# IO_Carte_Nucleo2.net
KiCad netlist of a schematic drawn in Altium Designer
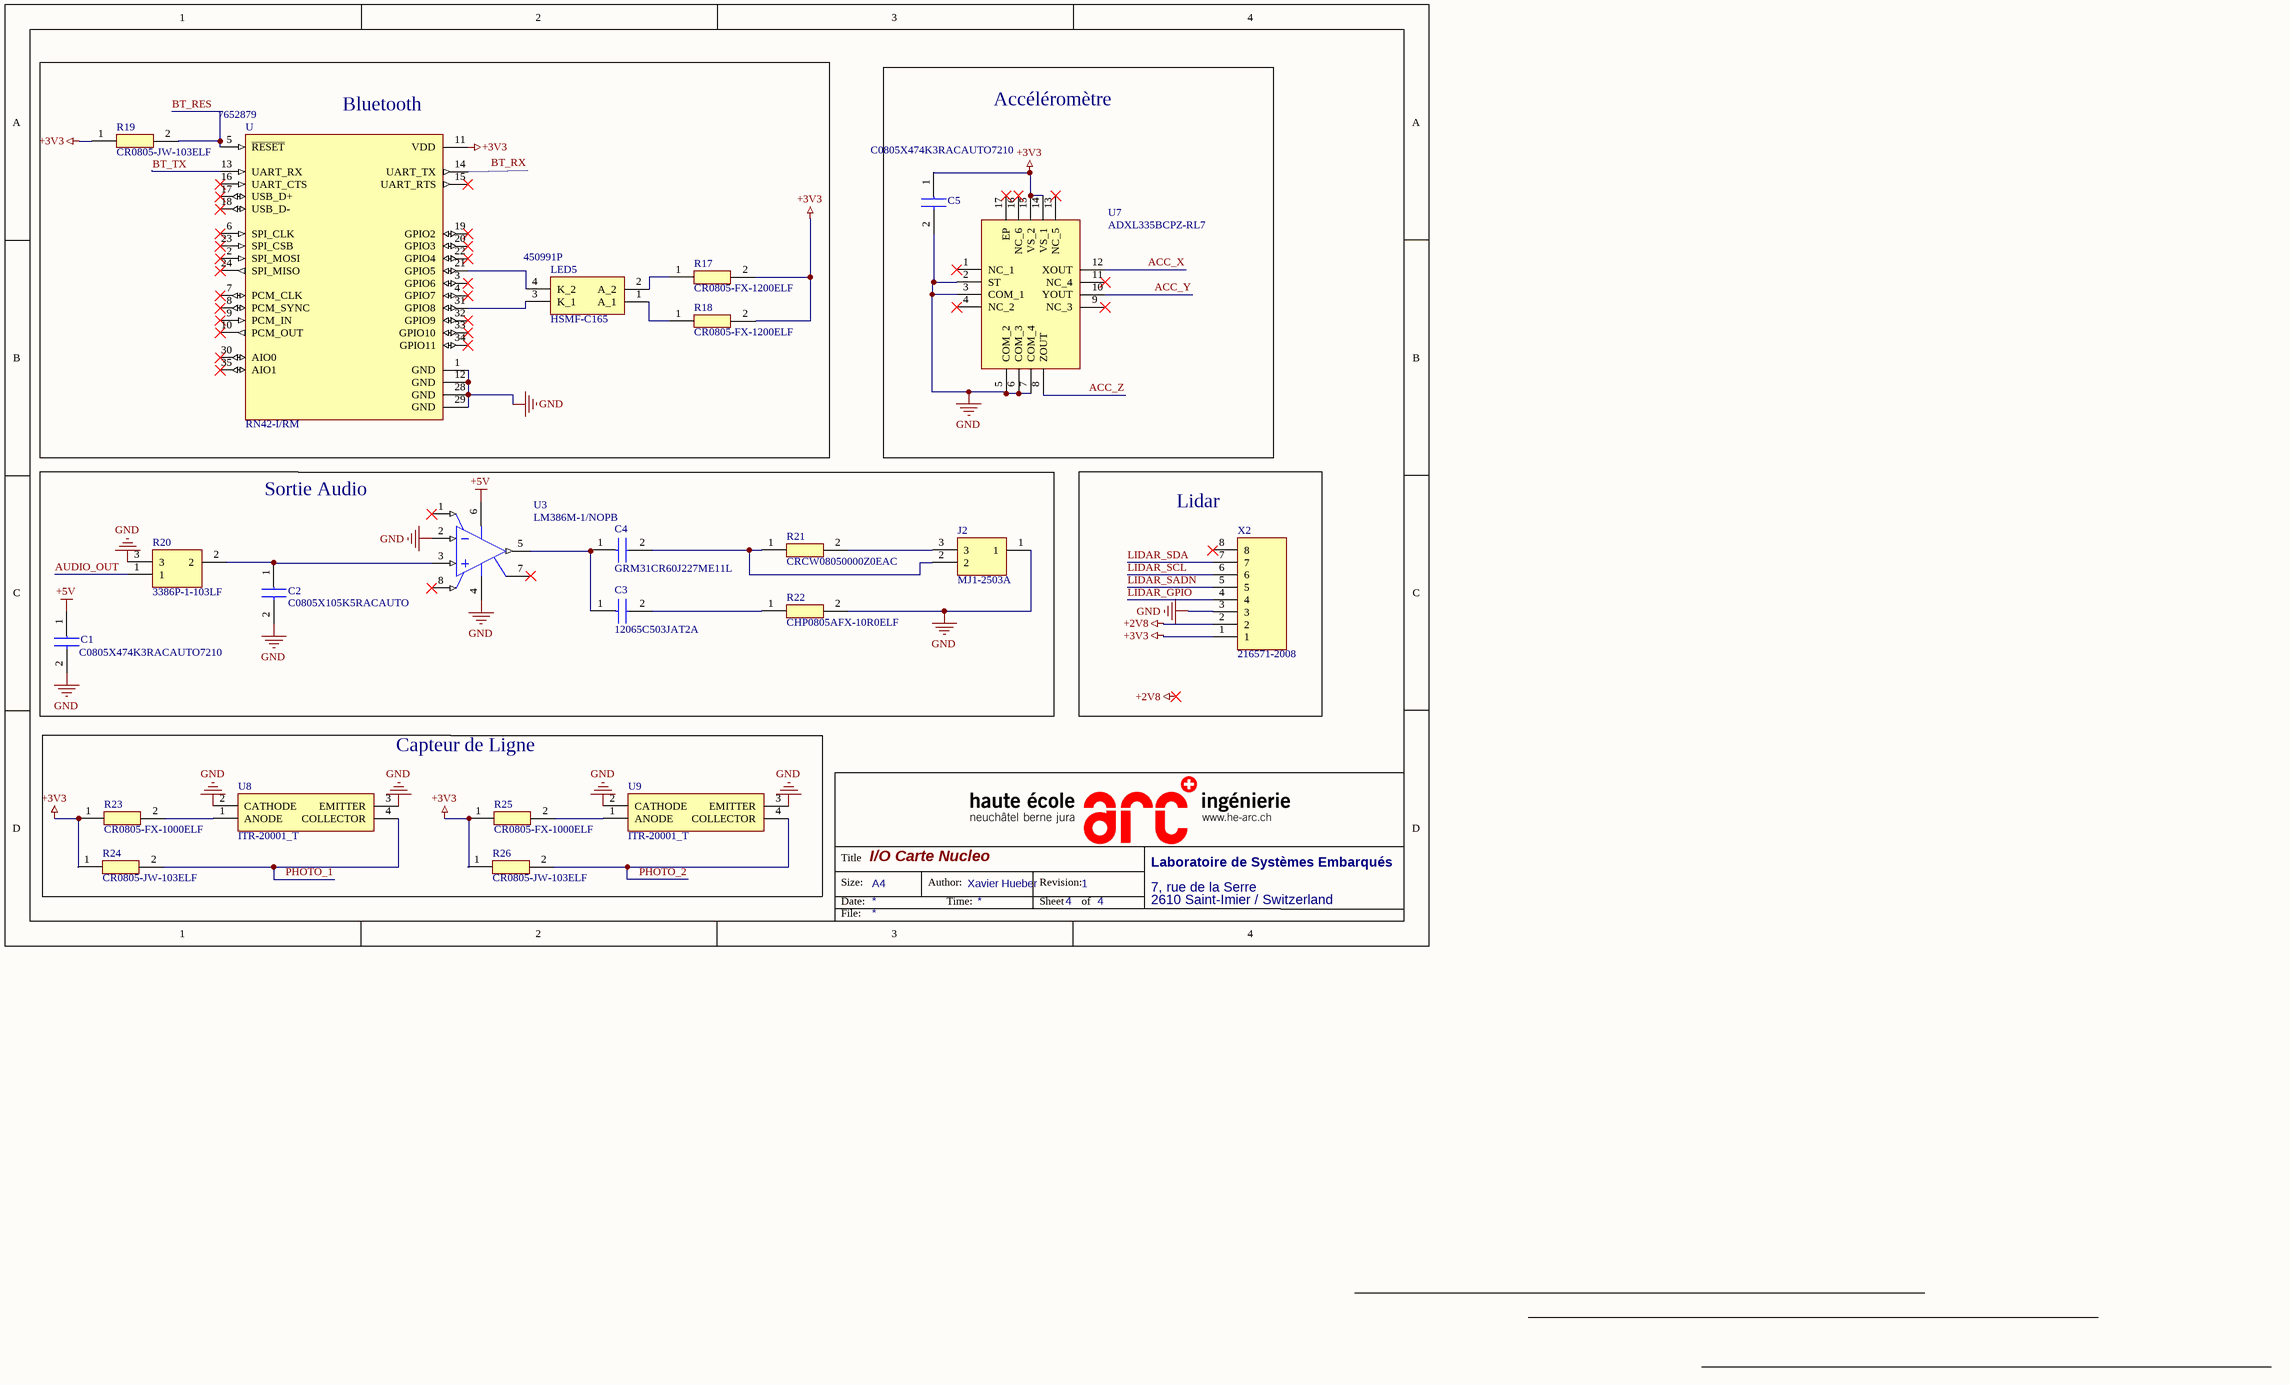
[diagram p0: IO_Carte_Nucleo2.SchDoc]

(export (version "E")
  (design (tool "Eeschema 10.0.6"))
  (components
    (comp (ref "C1")
      (value "C0805X474K3RACAUTO7210")
      (footprint "SamacSys:C0805")
      (description "Capacitor")
      (libsource (lib "*") (part "C0805X474K3RACAUTO7210"))
    )
    (comp (ref "C2")
      (value "C0805X105K5RACAUTO")
      (footprint "SamacSys:CAPC2012X145N")
      (description "Capacitor")
      (libsource (lib "*") (part "C0805X105K5RACAUTO"))
    )
    (comp (ref "C3")
      (value "12065C503JAT2A")
      (footprint "SamacSys:CAPC3216X94N")
      (description "Capacitor")
      (libsource (lib "*") (part "12065C503JAT2A"))
    )
    (comp (ref "C4")
      (value "GRM31CR60J227ME11L")
      (footprint "SamacSys:CAPC3216X190N")
      (description "Capacitor")
      (libsource (lib "*") (part "GRM31CR60J227ME11L"))
    )
    (comp (ref "C5")
      (value "C0805X474K3RACAUTO7210")
      (footprint "SamacSys:C0805")
      (description "Capacitor")
      (libsource (lib "*") (part "C0805X474K3RACAUTO7210"))
    )
    (comp (ref "J2")
      (value "MJ1-2503A")
      (footprint "SamacSys:MJ12503A")
      (description "Connector")
      (fields (field (name "MOUSER2 PART NUMBER") "490-MJ1-2503A"))
      (libsource (lib "*") (part "MJ1-2503A"))
    )
    (comp (ref "LED5")
      (value "HSMF-C165")
      (footprint "SamacSys:HSMF-C163")
      (description "LED Bi-Color Green/Red 570nm/636nm 4-Pin Chip 0603 T/R")
      (fields
        (field (name "MOUSER2 PART NUMBER") "630-HSMF-C165")
        (field (name "SUPPLIER PART NUMBER 1") "450991P")
      )
      (libsource (lib "*") (part "HSMF-C165"))
    )
    (comp (ref "R17")
      (value "CR0805-FX-1200ELF")
      (footprint "SamacSys:RESC2012X60N")
      (description "Resistor")
      (libsource (lib "*") (part "CR0805-FX-1200ELF"))
    )
    (comp (ref "R18")
      (value "CR0805-FX-1200ELF")
      (footprint "SamacSys:RESC2012X60N")
      (description "Resistor")
      (libsource (lib "*") (part "CR0805-FX-1200ELF"))
    )
    (comp (ref "R19")
      (value "CR0805-JW-103ELF")
      (footprint "SamacSys:RESC2012X60N")
      (libsource (lib "*") (part "CR0805-JW-103ELF"))
    )
    (comp (ref "R20")
      (value "3386P-1-103LF")
      (footprint "SamacSys:3386P_1")
      (description "Resistor")
      (fields (field (name "MOUSER2 PART NUMBER") "652-3386P-1-103LF"))
      (libsource (lib "*") (part "3386P-1-103LF"))
    )
    (comp (ref "R21")
      (value "CRCW08050000Z0EAC")
      (footprint "SamacSys:RESC2012X60N")
      (description "Resistor")
      (fields (field (name "MOUSER2 PART NUMBER") "71-CRCW08050000Z0EAC"))
      (libsource (lib "*") (part "CRCW08050000Z0EAC"))
    )
    (comp (ref "R22")
      (value "CHP0805AFX-10R0ELF")
      (footprint "SamacSys:RESC2012X60N")
      (description "Resistor")
      (libsource (lib "*") (part "CHP0805AFX-10R0ELF"))
    )
    (comp (ref "R23")
      (value "CR0805-FX-1000ELF")
      (footprint "SamacSys:RESC2012X60N")
      (description "Resistor")
      (libsource (lib "*") (part "CR0805-FX-1000ELF"))
    )
    (comp (ref "R24")
      (value "CR0805-JW-103ELF")
      (footprint "SamacSys:RESC2012X60N")
      (description "Resistor")
      (fields (field (name "MOUSER2 PART NUMBER") "652-CR0805-JW-103ELF"))
      (libsource (lib "*") (part "CR0805-JW-103ELF"))
    )
    (comp (ref "R25")
      (value "CR0805-FX-1000ELF")
      (footprint "SamacSys:RESC2012X60N")
      (description "Resistor")
      (libsource (lib "*") (part "CR0805-FX-1000ELF"))
    )
    (comp (ref "R26")
      (value "CR0805-JW-103ELF")
      (footprint "SamacSys:RESC2012X60N")
      (description "Resistor")
      (fields (field (name "MOUSER2 PART NUMBER") "652-CR0805-JW-103ELF"))
      (libsource (lib "*") (part "CR0805-JW-103ELF"))
    )
    (comp (ref "U")
      (value "RN42-I/RM")
      (footprint "XCVR_RN42-I/RM")
      (description "Bluetooth Bluetooth v2.1 +EDR, Class 2 Transceiver Module 2.4GHz Integrated, Trace Surface Mount")
      (fields (field (name "MF") "Microchip") (field (name "SUPPLIER PART NUMBER 1") "7652879"))
      (libsource (lib "SnapEDAsch") (part "RN42-I/RM"))
    )
    (comp (ref "U3")
      (value "LM386M-1/NOPB")
      (footprint "TI-D8_M")
      (description "Low Voltage Audio Power Amplifier, 0 to 70 degC, 8-pin SOIC (D8), Green (RoHS & no Sb/Br)")
      (fields (field (name "MANUFACTURER") "Texas Instruments"))
      (libsource (lib "Altium Content Vault") (part "TI-LM386undefined"))
    )
    (comp (ref "U7")
      (value "ADXL335BCPZ-RL7")
      (footprint "SamacSys:QFN65P400X400X150-17N-D")
      (description "Integrated Circuit")
      (fields (field (name "MOUSER2 PART NUMBER") "584-ADXL335BCPZ-R7"))
      (libsource (lib "*") (part "ADXL335BCPZ-RL7"))
    )
    (comp (ref "U8")
      (value "ITR-20001_T")
      (footprint "SamacSys:ITR20001T")
      (description "Undefined or Miscellaneous")
      (fields (field (name "MANUFACTURER_PART_NUMBER") "ITR-20001/T"))
      (libsource (lib "*") (part "ITR-20001_T"))
    )
    (comp (ref "U9")
      (value "ITR-20001_T")
      (footprint "SamacSys:ITR20001T")
      (description "Undefined or Miscellaneous")
      (fields (field (name "MANUFACTURER_PART_NUMBER") "ITR-20001/T"))
      (libsource (lib "*") (part "ITR-20001_T"))
    )
    (comp (ref "X2")
      (value "216571-2008")
      (footprint "SamacSys:216571-YY08")
      (description "Connector")
      (libsource (lib "*") (part "216571-2008"))
    )
  )
  (nets
    (net (code "1") (name "+2V8") (class "Default")
      (node (ref "X2") (pin "2") (pinfunction "2_2") (pintype "passive"))
    )
    (net (code "2") (name "+3V3") (class "Default")
      (node (ref "C5") (pin "1") (pinfunction "1_1") (pintype "passive"))
      (node (ref "R17") (pin "2") (pinfunction "2_2") (pintype "passive"))
      (node (ref "R18") (pin "2") (pinfunction "2_2") (pintype "passive"))
      (node (ref "R19") (pin "1") (pinfunction "1_1") (pintype "passive"))
      (node (ref "R23") (pin "1") (pinfunction "1_1") (pintype "passive"))
      (node (ref "R24") (pin "1") (pinfunction "1_1") (pintype "passive"))
      (node (ref "R25") (pin "1") (pinfunction "1_1") (pintype "passive"))
      (node (ref "R26") (pin "1") (pinfunction "1_1") (pintype "passive"))
      (node (ref "U") (pin "11") (pinfunction "VDD_11") (pintype "power_in"))
      (node (ref "U7") (pin "14") (pinfunction "VS_1_14") (pintype "passive"))
      (node (ref "U7") (pin "15") (pinfunction "VS_2_15") (pintype "passive"))
      (node (ref "X2") (pin "1") (pinfunction "1_1") (pintype "passive"))
    )
    (net (code "3") (name "+5V") (class "Default")
      (node (ref "C1") (pin "1") (pinfunction "1_1") (pintype "passive"))
      (node (ref "U3") (pin "6") (pinfunction "VS_6") (pintype "power_in"))
    )
    (net (code "4") (name "/ACC_X") (class "Default")
      (node (ref "U7") (pin "12") (pinfunction "XOUT_12") (pintype "passive"))
    )
    (net (code "5") (name "/ACC_Y") (class "Default")
      (node (ref "U7") (pin "10") (pinfunction "YOUT_10") (pintype "passive"))
    )
    (net (code "6") (name "/ACC_Z") (class "Default")
      (node (ref "U7") (pin "8") (pinfunction "ZOUT_8") (pintype "passive"))
    )
    (net (code "7") (name "/AUDIO_OUT") (class "Default")
      (node (ref "R20") (pin "1") (pinfunction "1_1") (pintype "passive"))
    )
    (net (code "8") (name "/BT_RES") (class "Default")
      (node (ref "R19") (pin "2") (pinfunction "2_2") (pintype "passive"))
      (node (ref "U") (pin "5") (pinfunction "~{RESET}_5") (pintype "input"))
    )
    (net (code "9") (name "/BT_RX") (class "Default")
      (node (ref "U") (pin "14") (pinfunction "UART_TX_14") (pintype "output"))
    )
    (net (code "10") (name "/BT_TX") (class "Default")
      (node (ref "U") (pin "13") (pinfunction "UART_RX_13") (pintype "input"))
    )
    (net (code "11") (name "/LIDAR_GPIO") (class "Default")
      (node (ref "X2") (pin "4") (pinfunction "4_4") (pintype "passive"))
    )
    (net (code "12") (name "/LIDAR_SADN") (class "Default")
      (node (ref "X2") (pin "5") (pinfunction "5_5") (pintype "passive"))
    )
    (net (code "13") (name "/LIDAR_SCL") (class "Default")
      (node (ref "X2") (pin "6") (pinfunction "6_6") (pintype "passive"))
    )
    (net (code "14") (name "/LIDAR_SDA") (class "Default")
      (node (ref "X2") (pin "7") (pinfunction "7_7") (pintype "passive"))
    )
    (net (code "15") (name "/PHOTO_1") (class "Default")
      (node (ref "R24") (pin "2") (pinfunction "2_2") (pintype "passive"))
      (node (ref "U8") (pin "4") (pinfunction "COLLECTOR_4") (pintype "passive"))
    )
    (net (code "16") (name "/PHOTO_2") (class "Default")
      (node (ref "R26") (pin "2") (pinfunction "2_2") (pintype "passive"))
      (node (ref "U9") (pin "4") (pinfunction "COLLECTOR_4") (pintype "passive"))
    )
    (net (code "17") (name "GND") (class "Default")
      (node (ref "C1") (pin "2") (pinfunction "2_2") (pintype "passive"))
      (node (ref "C2") (pin "2") (pinfunction "2_2") (pintype "passive"))
      (node (ref "C5") (pin "2") (pinfunction "2_2") (pintype "passive"))
      (node (ref "J2") (pin "1") (pinfunction "1_1") (pintype "passive"))
      (node (ref "R20") (pin "3") (pinfunction "3_3") (pintype "passive"))
      (node (ref "R22") (pin "2") (pinfunction "2_2") (pintype "passive"))
      (node (ref "U") (pin "1") (pinfunction "GND_1") (pintype "power_in"))
      (node (ref "U") (pin "12") (pinfunction "GND_12") (pintype "power_in"))
      (node (ref "U") (pin "28") (pinfunction "GND_28") (pintype "power_in"))
      (node (ref "U") (pin "29") (pinfunction "GND_29") (pintype "power_in"))
      (node (ref "U3") (pin "2") (pinfunction "IN-_2") (pintype "input"))
      (node (ref "U3") (pin "4") (pinfunction "GND_4") (pintype "power_in"))
      (node (ref "U7") (pin "2") (pinfunction "ST_2") (pintype "passive"))
      (node (ref "U7") (pin "3") (pinfunction "COM_1_3") (pintype "passive"))
      (node (ref "U7") (pin "5") (pinfunction "COM_2_5") (pintype "passive"))
      (node (ref "U7") (pin "6") (pinfunction "COM_3_6") (pintype "passive"))
      (node (ref "U7") (pin "7") (pinfunction "COM_4_7") (pintype "passive"))
      (node (ref "U8") (pin "2") (pinfunction "CATHODE_2") (pintype "passive"))
      (node (ref "U8") (pin "3") (pinfunction "EMITTER_3") (pintype "passive"))
      (node (ref "U9") (pin "2") (pinfunction "CATHODE_2") (pintype "passive"))
      (node (ref "U9") (pin "3") (pinfunction "EMITTER_3") (pintype "passive"))
      (node (ref "X2") (pin "3") (pinfunction "3_3") (pintype "passive"))
    )
    (net (code "18") (name "Net-(C3-C1)") (class "Default")
      (node (ref "C3") (pin "1") (pinfunction "C1_1") (pintype "passive"))
      (node (ref "C4") (pin "1") (pinfunction "1_1") (pintype "passive"))
      (node (ref "U3") (pin "5") (pinfunction "VOUT_5") (pintype "output"))
    )
    (net (code "19") (name "Net-(C3-C2)") (class "Default")
      (node (ref "C3") (pin "2") (pinfunction "C2_2") (pintype "passive"))
      (node (ref "R22") (pin "1") (pinfunction "1_1") (pintype "passive"))
    )
    (net (code "20") (name "Net-(C4-Pad2)") (class "Default")
      (node (ref "C4") (pin "2") (pinfunction "2_2") (pintype "passive"))
      (node (ref "J2") (pin "2") (pinfunction "2_2") (pintype "passive"))
      (node (ref "R21") (pin "1") (pinfunction "1_1") (pintype "passive"))
    )
    (net (code "21") (name "Net-(J2-Pad3)") (class "Default")
      (node (ref "J2") (pin "3") (pinfunction "3_3") (pintype "passive"))
      (node (ref "R21") (pin "2") (pinfunction "2_2") (pintype "passive"))
    )
    (net (code "22") (name "Net-(LED5-A_1)") (class "Default")
      (node (ref "LED5") (pin "1") (pinfunction "A_1_1") (pintype "passive"))
      (node (ref "R18") (pin "1") (pinfunction "1_1") (pintype "passive"))
    )
    (net (code "23") (name "Net-(LED5-A_2)") (class "Default")
      (node (ref "LED5") (pin "2") (pinfunction "A_2_2") (pintype "passive"))
      (node (ref "R17") (pin "1") (pinfunction "1_1") (pintype "passive"))
    )
    (net (code "24") (name "Net-(LED5-K_1)") (class "Default")
      (node (ref "LED5") (pin "3") (pinfunction "K_1_3") (pintype "passive"))
      (node (ref "U") (pin "31") (pinfunction "GPIO8_31") (pintype "bidirectional"))
    )
    (net (code "25") (name "Net-(LED5-K_2)") (class "Default")
      (node (ref "LED5") (pin "4") (pinfunction "K_2_4") (pintype "passive"))
      (node (ref "U") (pin "21") (pinfunction "GPIO5_21") (pintype "bidirectional"))
    )
    (net (code "26") (name "Net-(U3-IN+)") (class "Default")
      (node (ref "C2") (pin "1") (pinfunction "1_1") (pintype "passive"))
      (node (ref "R20") (pin "2") (pinfunction "2_2") (pintype "passive"))
      (node (ref "U3") (pin "3") (pinfunction "IN+_3") (pintype "input"))
    )
    (net (code "27") (name "Net-(U8-ANODE)") (class "Default")
      (node (ref "R23") (pin "2") (pinfunction "2_2") (pintype "passive"))
      (node (ref "U8") (pin "1") (pinfunction "ANODE_1") (pintype "passive"))
    )
    (net (code "28") (name "Net-(U9-ANODE)") (class "Default")
      (node (ref "R25") (pin "2") (pinfunction "2_2") (pintype "passive"))
      (node (ref "U9") (pin "1") (pinfunction "ANODE_1") (pintype "passive"))
    )
    (net (code "29") (name "unconnected-(U-AIO0-Pad30)") (class "Default")
      (node (ref "U") (pin "30") (pinfunction "AIO0_30") (pintype "bidirectional+no_connect"))
    )
    (net (code "30") (name "unconnected-(U-AIO1-Pad35)") (class "Default")
      (node (ref "U") (pin "35") (pinfunction "AIO1_35") (pintype "bidirectional+no_connect"))
    )
    (net (code "31") (name "unconnected-(U-GPIO2-Pad19)") (class "Default")
      (node (ref "U") (pin "19") (pinfunction "GPIO2_19") (pintype "bidirectional+no_connect"))
    )
    (net (code "32") (name "unconnected-(U-GPIO3-Pad20)") (class "Default")
      (node (ref "U") (pin "20") (pinfunction "GPIO3_20") (pintype "bidirectional+no_connect"))
    )
    (net (code "33") (name "unconnected-(U-GPIO4-Pad22)") (class "Default")
      (node (ref "U") (pin "22") (pinfunction "GPIO4_22") (pintype "bidirectional+no_connect"))
    )
    (net (code "34") (name "unconnected-(U-GPIO6-Pad3)") (class "Default")
      (node (ref "U") (pin "3") (pinfunction "GPIO6_3") (pintype "bidirectional+no_connect"))
    )
    (net (code "35") (name "unconnected-(U-GPIO7-Pad4)") (class "Default")
      (node (ref "U") (pin "4") (pinfunction "GPIO7_4") (pintype "bidirectional+no_connect"))
    )
    (net (code "36") (name "unconnected-(U-GPIO9-Pad32)") (class "Default")
      (node (ref "U") (pin "32") (pinfunction "GPIO9_32") (pintype "bidirectional+no_connect"))
    )
    (net (code "37") (name "unconnected-(U-GPIO10-Pad33)") (class "Default")
      (node (ref "U") (pin "33") (pinfunction "GPIO10_33") (pintype "bidirectional+no_connect"))
    )
    (net (code "38") (name "unconnected-(U-GPIO11-Pad34)") (class "Default")
      (node (ref "U") (pin "34") (pinfunction "GPIO11_34") (pintype "bidirectional+no_connect"))
    )
    (net (code "39") (name "unconnected-(U-PCM_CLK-Pad7)") (class "Default")
      (node (ref "U") (pin "7") (pinfunction "PCM_CLK_7") (pintype "bidirectional+no_connect"))
    )
    (net (code "40") (name "unconnected-(U-PCM_IN-Pad9)") (class "Default")
      (node (ref "U") (pin "9") (pinfunction "PCM_IN_9") (pintype "input+no_connect"))
    )
    (net (code "41") (name "unconnected-(U-PCM_OUT-Pad10)") (class "Default")
      (node (ref "U") (pin "10") (pinfunction "PCM_OUT_10") (pintype "output+no_connect"))
    )
    (net (code "42") (name "unconnected-(U-PCM_SYNC-Pad8)") (class "Default")
      (node (ref "U") (pin "8") (pinfunction "PCM_SYNC_8") (pintype "bidirectional+no_connect"))
    )
    (net (code "43") (name "unconnected-(U-SPI_CLK-Pad6)") (class "Default")
      (node (ref "U") (pin "6") (pinfunction "SPI_CLK_6") (pintype "input+no_connect"))
    )
    (net (code "44") (name "unconnected-(U-SPI_CSB-Pad23)") (class "Default")
      (node (ref "U") (pin "23") (pinfunction "SPI_CSB_23") (pintype "input+no_connect"))
    )
    (net (code "45") (name "unconnected-(U-SPI_MISO-Pad24)") (class "Default")
      (node (ref "U") (pin "24") (pinfunction "SPI_MISO_24") (pintype "output+no_connect"))
    )
    (net (code "46") (name "unconnected-(U-SPI_MOSI-Pad2)") (class "Default")
      (node (ref "U") (pin "2") (pinfunction "SPI_MOSI_2") (pintype "input+no_connect"))
    )
    (net (code "47") (name "unconnected-(U-UART_CTS-Pad16)") (class "Default")
      (node (ref "U") (pin "16") (pinfunction "UART_CTS_16") (pintype "input+no_connect"))
    )
    (net (code "48") (name "unconnected-(U-UART_RTS-Pad15)") (class "Default")
      (node (ref "U") (pin "15") (pinfunction "UART_RTS_15") (pintype "output+no_connect"))
    )
    (net (code "49") (name "unconnected-(U-USB_D+-Pad17)") (class "Default")
      (node (ref "U") (pin "17") (pinfunction "USB_D+_17") (pintype "bidirectional+no_connect"))
    )
    (net (code "50") (name "unconnected-(U-USB_D--Pad18)") (class "Default")
      (node (ref "U") (pin "18") (pinfunction "USB_D-_18") (pintype "bidirectional+no_connect"))
    )
    (net (code "51") (name "unconnected-(U3-BYPASS-Pad7)") (class "Default")
      (node (ref "U3") (pin "7") (pinfunction "BYPASS_7") (pintype "passive+no_connect"))
    )
    (net (code "52") (name "unconnected-(U3-GAIN-Pad1)") (class "Default")
      (node (ref "U3") (pin "1") (pinfunction "GAIN_1") (pintype "input+no_connect"))
    )
    (net (code "53") (name "unconnected-(U3-GAIN-Pad8)") (class "Default")
      (node (ref "U3") (pin "8") (pinfunction "GAIN_8") (pintype "input+no_connect"))
    )
    (net (code "54") (name "unconnected-(U7-EP-Pad17)") (class "Default")
      (node (ref "U7") (pin "17") (pinfunction "EP_17") (pintype "passive+no_connect"))
    )
    (net (code "55") (name "unconnected-(U7-NC_1-Pad1)") (class "Default")
      (node (ref "U7") (pin "1") (pinfunction "NC_1_1") (pintype "passive+no_connect"))
    )
    (net (code "56") (name "unconnected-(U7-NC_2-Pad4)") (class "Default")
      (node (ref "U7") (pin "4") (pinfunction "NC_2_4") (pintype "passive+no_connect"))
    )
    (net (code "57") (name "unconnected-(U7-NC_3-Pad9)") (class "Default")
      (node (ref "U7") (pin "9") (pinfunction "NC_3_9") (pintype "passive+no_connect"))
    )
    (net (code "58") (name "unconnected-(U7-NC_4-Pad11)") (class "Default")
      (node (ref "U7") (pin "11") (pinfunction "NC_4_11") (pintype "passive+no_connect"))
    )
    (net (code "59") (name "unconnected-(U7-NC_5-Pad13)") (class "Default")
      (node (ref "U7") (pin "13") (pinfunction "NC_5_13") (pintype "passive+no_connect"))
    )
    (net (code "60") (name "unconnected-(U7-NC_6-Pad16)") (class "Default")
      (node (ref "U7") (pin "16") (pinfunction "NC_6_16") (pintype "passive+no_connect"))
    )
    (net (code "61") (name "unconnected-(X2-Pad8)") (class "Default")
      (node (ref "X2") (pin "8") (pinfunction "8_8") (pintype "passive+no_connect"))
    )
  )
)
